# 04-POWER.net
KiCad netlist of a schematic drawn in Altium Designer
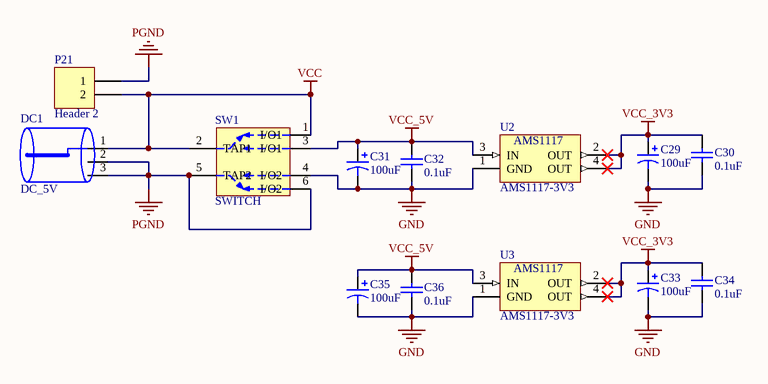
[diagram p0: 04-POWER.SchDoc]

(export (version "E")
  (design (tool "Eeschema 10.0.6"))
  (components
    (comp (ref "C29")
      (value "100uF")
      (footprint "C_SMD(6.3x5.3)")
      (description "Polarized Capacitor (Radial)")
      (fields (field (name "PUBLISHER") "Altium Limited"))
      (libsource (lib "Miscellaneous Devices") (part "Cap Pol1"))
    )
    (comp (ref "C30")
      (value "0.1uF")
      (footprint "0603C")
      (description "Capacitor")
      (fields (field (name "PUBLISHER") "Altium Limited"))
      (libsource (lib "Miscellaneous Devices") (part "Cap"))
    )
    (comp (ref "C31")
      (value "100uF")
      (footprint "C_SMD(6.3x5.3)")
      (description "Polarized Capacitor (Radial)")
      (fields (field (name "PUBLISHER") "Altium Limited"))
      (libsource (lib "Miscellaneous Devices") (part "Cap Pol1"))
    )
    (comp (ref "C32")
      (value "0.1uF")
      (footprint "0603C")
      (description "Capacitor")
      (fields (field (name "PUBLISHER") "Altium Limited"))
      (libsource (lib "Miscellaneous Devices") (part "Cap"))
    )
    (comp (ref "C33")
      (value "100uF")
      (footprint "C_SMD(6.3x5.3)")
      (description "Polarized Capacitor (Radial)")
      (fields (field (name "PUBLISHER") "Altium Limited"))
      (libsource (lib "Miscellaneous Devices") (part "Cap Pol1"))
    )
    (comp (ref "C34")
      (value "0.1uF")
      (footprint "0603C")
      (description "Capacitor")
      (fields (field (name "PUBLISHER") "Altium Limited"))
      (libsource (lib "Miscellaneous Devices") (part "Cap"))
    )
    (comp (ref "C35")
      (value "100uF")
      (footprint "C_SMD(6.3x5.3)")
      (description "Polarized Capacitor (Radial)")
      (fields (field (name "PUBLISHER") "Altium Limited"))
      (libsource (lib "Miscellaneous Devices") (part "Cap Pol1"))
    )
    (comp (ref "C36")
      (value "0.1uF")
      (footprint "0603C")
      (description "Capacitor")
      (fields (field (name "PUBLISHER") "Altium Limited"))
      (libsource (lib "Miscellaneous Devices") (part "Cap"))
    )
    (comp (ref "DC1")
      (value "DC_5V")
      (footprint "DC_POWER")
      (description "DC005")
      (fields
        (field (name "MANUFACTURER") "TruConnect")
        (field (name "MANUFACTURER PART NUMBER") "K-DC-0052.5")
      )
      (libsource (lib "Desiger_Schlib") (part "DC_5V"))
    )
    (comp (ref "P21")
      (value "Header 2")
      (footprint "KF2EDG_3R81_2P")
      (description "Header, 2-Pin")
      (fields (field (name "PUBLISHER") "Altium Limited"))
      (libsource (lib "Miscellaneous Connectors") (part "Header 2"))
    )
    (comp (ref "SW1")
      (value "SWITCH")
      (footprint "Desiger_Pcblib:SW-8R5X8R5")
      (libsource (lib "Desiger_Schlib") (part "SWITCH"))
    )
    (comp (ref "U2")
      (value "AMS1117-3V3")
      (footprint "Desiger_Pcblib:SOT223")
      (libsource (lib "Desiger_Schlib") (part "AMS1117-3v3"))
    )
    (comp (ref "U3")
      (value "AMS1117-3V3")
      (footprint "Desiger_Pcblib:SOT223")
      (libsource (lib "Desiger_Schlib") (part "AMS1117-3v3"))
    )
  )
  (nets
    (net (code "1") (name "GND") (class "Default")
      (node (ref "C29") (pin "2") (pinfunction "2_2") (pintype "passive"))
      (node (ref "C30") (pin "1") (pinfunction "1_1") (pintype "passive"))
      (node (ref "C31") (pin "2") (pinfunction "2_2") (pintype "passive"))
      (node (ref "C32") (pin "1") (pinfunction "1_1") (pintype "passive"))
      (node (ref "C33") (pin "2") (pinfunction "2_2") (pintype "passive"))
      (node (ref "C34") (pin "1") (pinfunction "1_1") (pintype "passive"))
      (node (ref "C35") (pin "2") (pinfunction "2_2") (pintype "passive"))
      (node (ref "C36") (pin "1") (pinfunction "1_1") (pintype "passive"))
      (node (ref "SW1") (pin "4") (pinfunction "I/O2_4") (pintype "passive"))
      (node (ref "U2") (pin "1") (pinfunction "GND_1") (pintype "power_in"))
      (node (ref "U3") (pin "1") (pinfunction "GND_1") (pintype "power_in"))
    )
    (net (code "2") (name "PGND") (class "Default")
      (node (ref "DC1") (pin "2") (pinfunction "VCC_2") (pintype "power_in"))
      (node (ref "DC1") (pin "3") (pinfunction "VCC_3") (pintype "power_in"))
      (node (ref "P21") (pin "1") (pinfunction "1_1") (pintype "passive"))
      (node (ref "SW1") (pin "5") (pinfunction "TAP2_5") (pintype "passive"))
      (node (ref "SW1") (pin "6") (pinfunction "I/O2_6") (pintype "passive"))
    )
    (net (code "3") (name "VCC") (class "Default")
      (node (ref "DC1") (pin "1") (pinfunction "VCC_1") (pintype "power_in"))
      (node (ref "P21") (pin "2") (pinfunction "2_2") (pintype "passive"))
      (node (ref "SW1") (pin "1") (pinfunction "I/O1_1") (pintype "passive"))
      (node (ref "SW1") (pin "2") (pinfunction "TAP1_2") (pintype "passive"))
    )
    (net (code "4") (name "VCC_3V3") (class "Default")
      (node (ref "C29") (pin "1") (pinfunction "1_1") (pintype "passive"))
      (node (ref "C30") (pin "2") (pinfunction "2_2") (pintype "passive"))
      (node (ref "C33") (pin "1") (pinfunction "1_1") (pintype "passive"))
      (node (ref "C34") (pin "2") (pinfunction "2_2") (pintype "passive"))
      (node (ref "U2") (pin "2") (pinfunction "OUT_2") (pintype "output"))
      (node (ref "U2") (pin "4") (pinfunction "OUT_4") (pintype "output"))
      (node (ref "U3") (pin "2") (pinfunction "OUT_2") (pintype "output"))
      (node (ref "U3") (pin "4") (pinfunction "OUT_4") (pintype "output"))
    )
    (net (code "5") (name "VCC_5V") (class "Default")
      (node (ref "C31") (pin "1") (pinfunction "1_1") (pintype "passive"))
      (node (ref "C32") (pin "2") (pinfunction "2_2") (pintype "passive"))
      (node (ref "C35") (pin "1") (pinfunction "1_1") (pintype "passive"))
      (node (ref "C36") (pin "2") (pinfunction "2_2") (pintype "passive"))
      (node (ref "SW1") (pin "3") (pinfunction "I/O1_3") (pintype "passive"))
      (node (ref "U2") (pin "3") (pinfunction "IN_3") (pintype "input"))
      (node (ref "U3") (pin "3") (pinfunction "IN_3") (pintype "input"))
    )
  )
)
